# Hvamp_32.net
KiCad netlist of a schematic drawn in Altium Designer
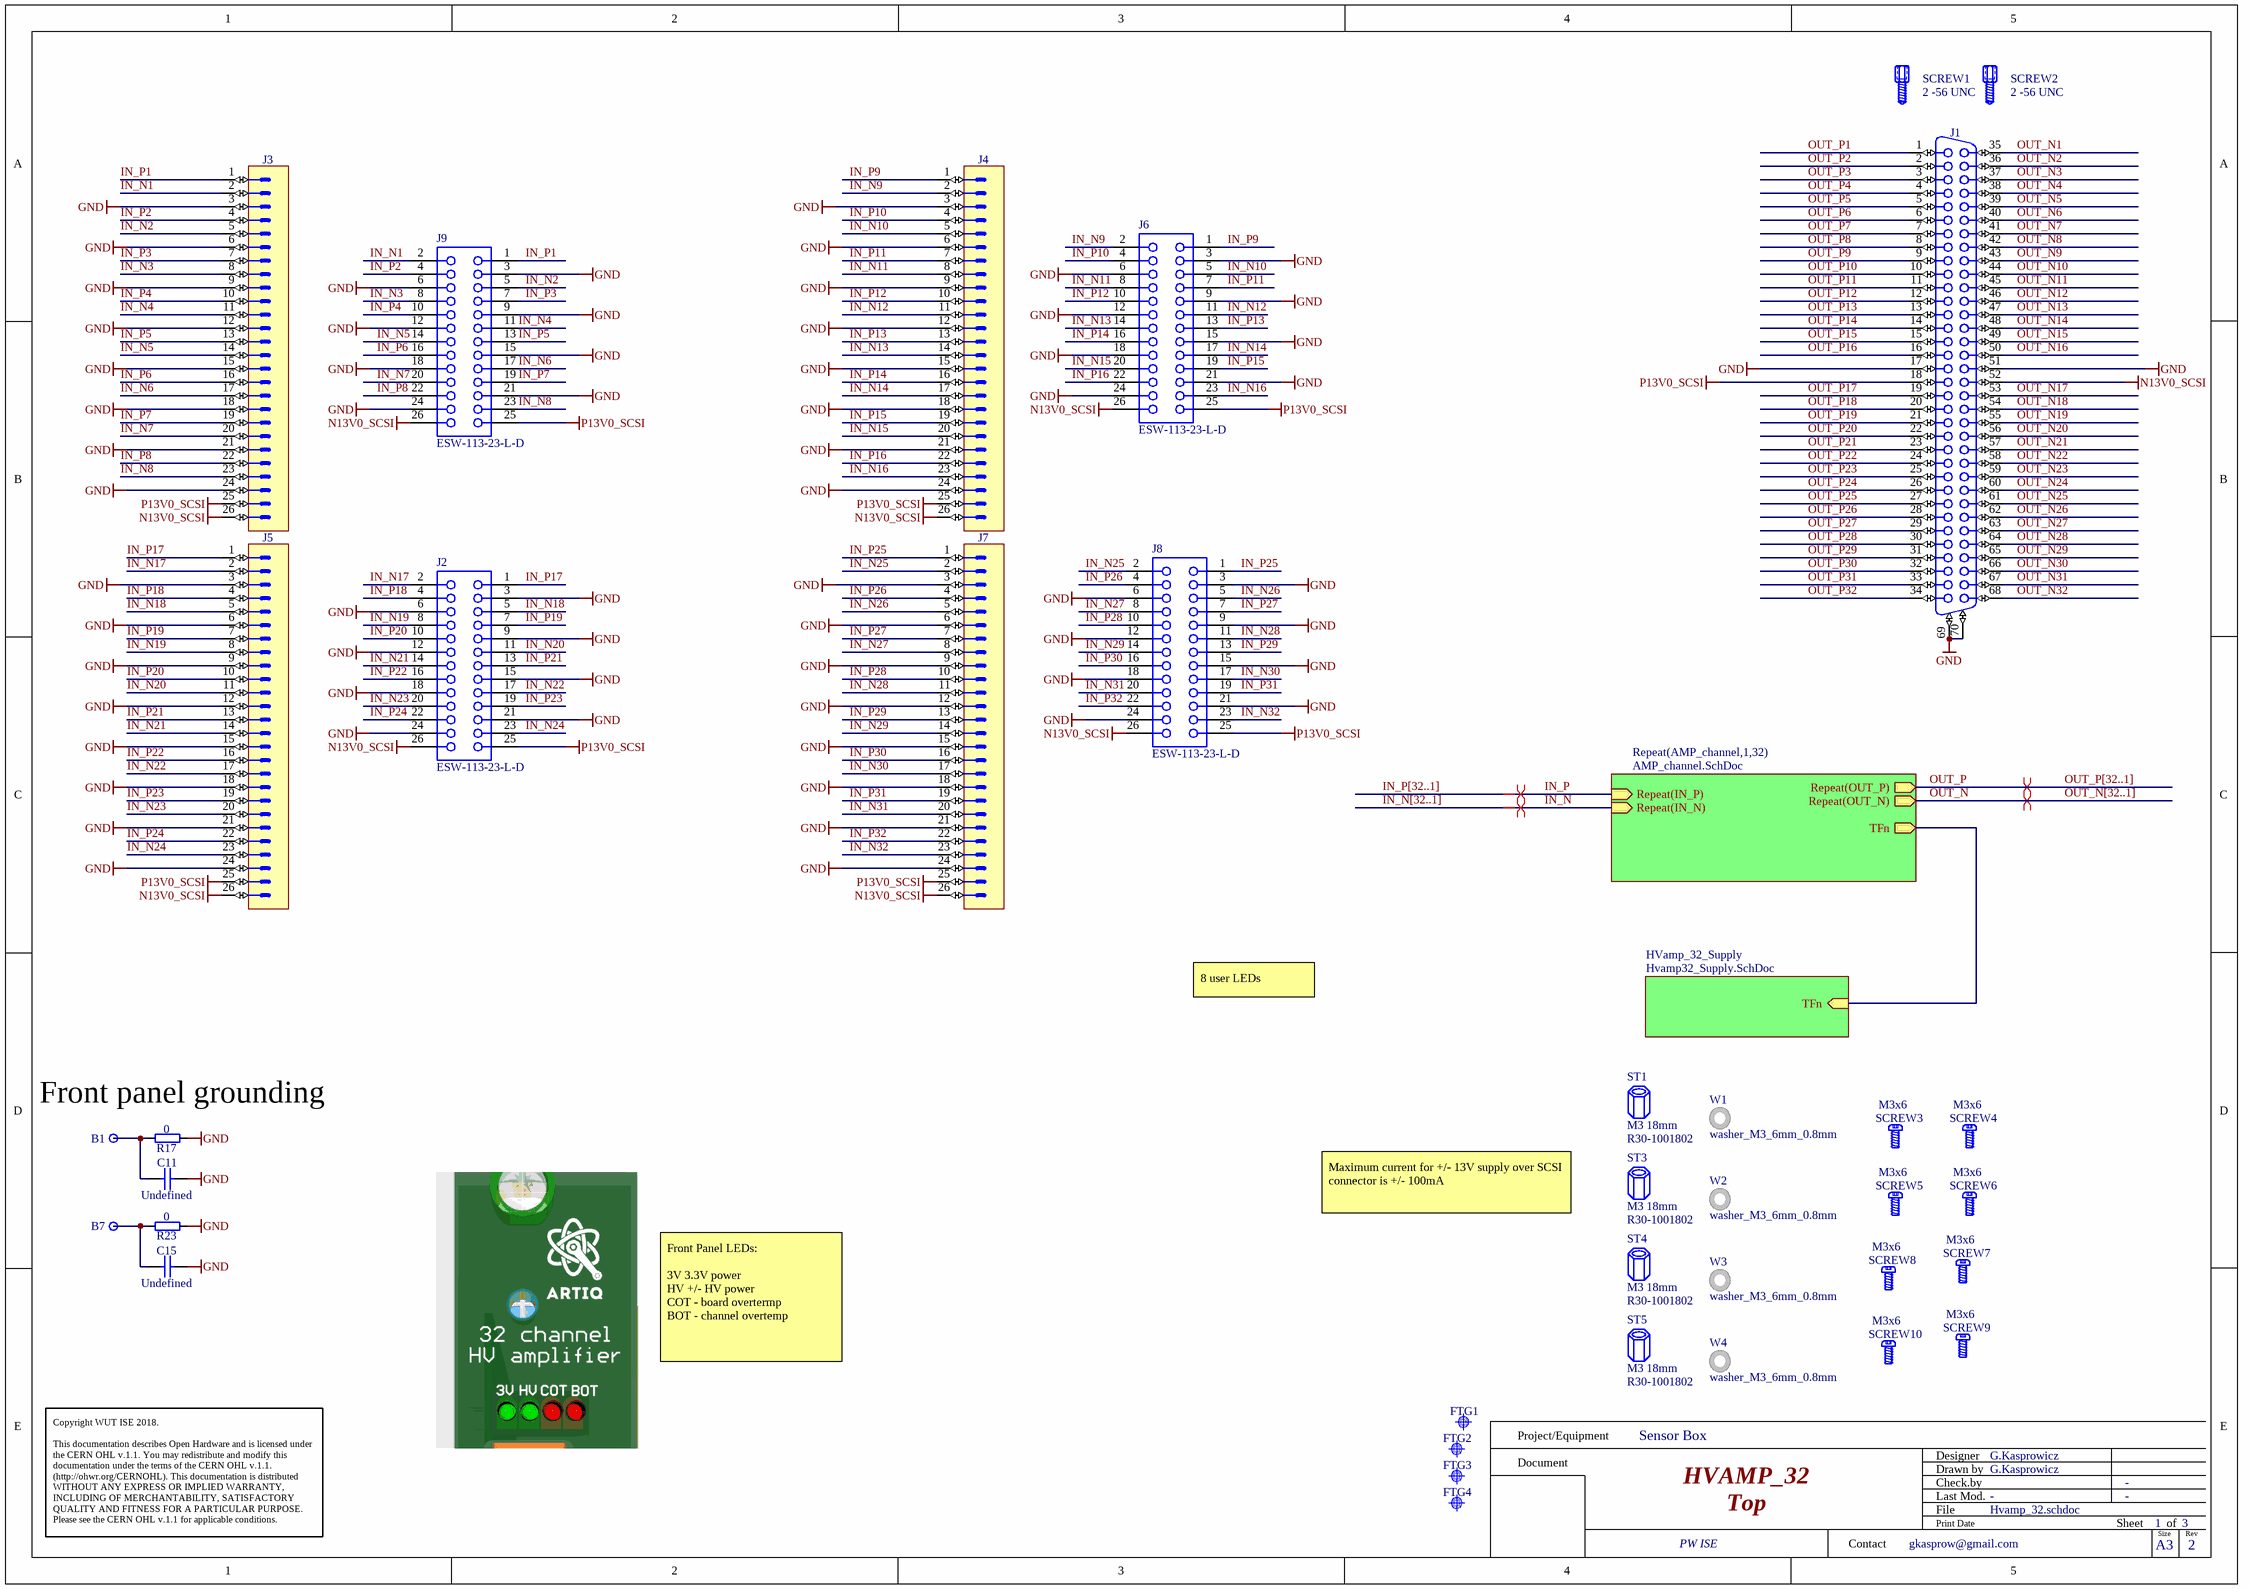
[diagram p0: Hvamp_32.schdoc]

(export (version "E")
  (design (tool "Eeschema 10.0.6"))
  (components
    (comp (ref "B1")
      (value "Plated Hole")
      (footprint "MTG270_500")
      (description "Single Terminal Socket")
      (fields (field (name "PART NUMBER") "PLATED_HOLE2.7_PAD5.0") (field (name "AUTHOR") "CERN DEM JMW"))
      (libsource (lib "Eletro-mechanical") (part "Single Terminal Socket"))
    )
    (comp (ref "B7")
      (value "Plated Hole")
      (footprint "MTG270_500")
      (description "Single Terminal Socket")
      (fields (field (name "PART NUMBER") "PLATED_HOLE2.7_PAD5.0") (field (name "AUTHOR") "CERN DEM JMW"))
      (libsource (lib "Eletro-mechanical") (part "Single Terminal Socket"))
    )
    (comp (ref "C11")
      (value "Undefined")
      (footprint "CAPC2012X135N")
      (description "Non-polarised capacitor")
      (fields (field (name "PART NUMBER") "CC0805_NO-VALUE") (field (name "AUTHOR") "CERN DEM JLC"))
      (libsource (lib "Capacitors") (part "Capacitor - non polarized"))
    )
    (comp (ref "C15")
      (value "Undefined")
      (footprint "CAPC2012X135N")
      (description "Non-polarised capacitor")
      (fields (field (name "PART NUMBER") "CC0805_NO-VALUE") (field (name "AUTHOR") "CERN DEM JLC"))
      (libsource (lib "Capacitors") (part "Capacitor - non polarized"))
    )
    (comp (ref "FTG1")
      (value "Use only in PCB")
      (footprint "FIDUCIAL_TOP_C100-200")
      (description "Fiducial Target")
      (fields (field (name "PART NUMBER") "FIDUCIAL_TARGET_C100-200") (field (name "AUTHOR") "CERN DEM JLC"))
      (libsource (lib "Eletro-mechanical") (part "Fiducial Target"))
    )
    (comp (ref "FTG2")
      (value "Use only in PCB")
      (footprint "FIDUCIAL_TOP_S100-200")
      (description "Fiducial Target")
      (fields (field (name "PART NUMBER") "FIDUCIAL_TARGET_S100-200") (field (name "AUTHOR") "CERN DEM JLC"))
      (libsource (lib "Eletro-mechanical") (part "Fiducial Target"))
    )
    (comp (ref "FTG3")
      (value "Use only in PCB")
      (footprint "FIDUCIAL_TOP_S100-200")
      (description "Fiducial Target")
      (fields (field (name "PART NUMBER") "FIDUCIAL_TARGET_S100-200") (field (name "AUTHOR") "CERN DEM JLC"))
      (libsource (lib "Eletro-mechanical") (part "Fiducial Target"))
    )
    (comp (ref "FTG4")
      (value "Use only in PCB")
      (footprint "FIDUCIAL_TOP_S100-200")
      (description "Fiducial Target")
      (fields (field (name "PART NUMBER") "FIDUCIAL_TARGET_S100-200") (field (name "AUTHOR") "CERN DEM JLC"))
      (libsource (lib "Eletro-mechanical") (part "Fiducial Target"))
    )
    (comp (ref "J1")
      (value "D-SUB")
      (footprint "TYCO_5787082-7")
      (description "68 contacts, AMPLIMITE .050\", Right Angled Receptacle Series III")
      (fields
        (field (name "PART NUMBER") "TYCO_5787082-7")
        (field (name "MANUFACTURER") "TYCO ELECTRONICS")
        (field (name "AUTHOR") "CERN DEM JLC")
      )
      (libsource (lib "Connectors") (part "TYCO_5787082-7"))
    )
    (comp (ref "J2")
      (value "ESW-113-23-L-D")
      (footprint "SMTC-ESW-113-23-X-D")
      (description "Elevated Socket, Through-hole, Vertical, -55 to 125 degC, 2.54 mm Pitch, 26-Pin, Female, RoHS")
      (fields (field (name "MANUFACTURER") "Samtec"))
      (libsource (lib "Altium Content Vault") (part "SMTC-ESW-113-X-X-D"))
    )
    (comp (ref "J3")
      (value "Header 26")
      (footprint "3M_N2526-6002RB")
      (description "Connector 26 Male")
      (fields
        (field (name "PART NUMBER") "3M_N2526-6002RB")
        (field (name "MANUFACTURER") "3M")
        (field (name "AUTHOR") "CERN DEM JLC")
      )
      (libsource (lib "Connectors") (part "Connector 26 Male"))
    )
    (comp (ref "J4")
      (value "Header 26")
      (footprint "3M_N2526-6002RB")
      (description "Connector 26 Male")
      (fields
        (field (name "PART NUMBER") "3M_N2526-6002RB")
        (field (name "MANUFACTURER") "3M")
        (field (name "AUTHOR") "CERN DEM JLC")
      )
      (libsource (lib "Connectors") (part "Connector 26 Male"))
    )
    (comp (ref "J5")
      (value "Header 26")
      (footprint "3M_N2526-6002RB")
      (description "Connector 26 Male")
      (fields
        (field (name "PART NUMBER") "3M_N2526-6002RB")
        (field (name "MANUFACTURER") "3M")
        (field (name "AUTHOR") "CERN DEM JLC")
      )
      (libsource (lib "Connectors") (part "Connector 26 Male"))
    )
    (comp (ref "J6")
      (value "ESW-113-23-L-D")
      (footprint "SMTC-ESW-113-23-X-D")
      (description "Elevated Socket, Through-hole, Vertical, -55 to 125 degC, 2.54 mm Pitch, 26-Pin, Female, RoHS")
      (fields (field (name "MANUFACTURER") "Samtec"))
      (libsource (lib "Altium Content Vault") (part "SMTC-ESW-113-X-X-D"))
    )
    (comp (ref "J7")
      (value "Header 26")
      (footprint "3M_N2526-6002RB")
      (description "Connector 26 Male")
      (fields
        (field (name "PART NUMBER") "3M_N2526-6002RB")
        (field (name "MANUFACTURER") "3M")
        (field (name "AUTHOR") "CERN DEM JLC")
      )
      (libsource (lib "Connectors") (part "Connector 26 Male"))
    )
    (comp (ref "J8")
      (value "ESW-113-23-L-D")
      (footprint "SMTC-ESW-113-23-X-D")
      (description "Elevated Socket, Through-hole, Vertical, -55 to 125 degC, 2.54 mm Pitch, 26-Pin, Female, RoHS")
      (fields (field (name "MANUFACTURER") "Samtec"))
      (libsource (lib "Altium Content Vault") (part "SMTC-ESW-113-X-X-D"))
    )
    (comp (ref "J9")
      (value "ESW-113-23-L-D")
      (footprint "SMTC-ESW-113-23-X-D")
      (description "Elevated Socket, Through-hole, Vertical, -55 to 125 degC, 2.54 mm Pitch, 26-Pin, Female, RoHS")
      (fields (field (name "MANUFACTURER") "Samtec"))
      (libsource (lib "Altium Content Vault") (part "SMTC-ESW-113-X-X-D"))
    )
    (comp (ref "R17")
      (value "0")
      (footprint "RESC1608X55N")
      (description "Resistor")
      (fields
        (field (name "PART NUMBER") "R0603_0R_JUMPER")
        (field (name "MANUFACTURER") "GENERIC")
        (field (name "AUTHOR") "CERN DEM JLC")
      )
      (libsource (lib "Resistors") (part "Resistor"))
    )
    (comp (ref "R23")
      (value "0")
      (footprint "RESC1608X55N")
      (description "Resistor")
      (fields
        (field (name "PART NUMBER") "R0603_0R_JUMPER")
        (field (name "MANUFACTURER") "GENERIC")
        (field (name "AUTHOR") "CERN DEM JLC")
      )
      (libsource (lib "Resistors") (part "Resistor"))
    )
    (comp (ref "SCREW1")
      (value "2 -56 UNC")
      (footprint "TYCO_786585-2")
      (description "SCSI Screw Lock")
      (fields
        (field (name "PART NUMBER") "TYCO_786585-2")
        (field (name "MANUFACTURER") "TYCO ELECTRONICS")
        (field (name "AUTHOR") "GK")
      )
      (libsource (lib "LIBRARY_SCH") (part "MECH_Tyco_SCSI_Screwlock"))
    )
    (comp (ref "SCREW2")
      (value "2 -56 UNC")
      (footprint "TYCO_786585-2")
      (description "SCSI Screw Lock")
      (fields
        (field (name "PART NUMBER") "TYCO_786585-2")
        (field (name "MANUFACTURER") "TYCO ELECTRONICS")
        (field (name "AUTHOR") "GK")
      )
      (libsource (lib "LIBRARY_SCH") (part "MECH_Tyco_SCSI_Screwlock"))
    )
    (comp (ref "SCREW3")
      (value "M3x6")
      (footprint "BOSSARD_BN5687-3061605_v")
      (description "Screw")
      (fields
        (field (name "PART NUMBER") "BOSSARD_BN5687-3061605_v")
        (field (name "MANUFACTURER") "BOSSARD")
        (field (name "AUTHOR") "CERN DEM JLC")
      )
      (libsource (lib "Eletro-mechanical") (part "Screw"))
    )
    (comp (ref "SCREW4")
      (value "M3x6")
      (footprint "BOSSARD_BN5687-3061605_v")
      (description "Screw")
      (fields
        (field (name "PART NUMBER") "BOSSARD_BN5687-3061605_v")
        (field (name "MANUFACTURER") "BOSSARD")
        (field (name "AUTHOR") "CERN DEM JLC")
      )
      (libsource (lib "Eletro-mechanical") (part "Screw"))
    )
    (comp (ref "SCREW5")
      (value "M3x6")
      (footprint "BOSSARD_BN5687-3061605_v")
      (description "Screw")
      (fields
        (field (name "PART NUMBER") "BOSSARD_BN5687-3061605_v")
        (field (name "MANUFACTURER") "BOSSARD")
        (field (name "AUTHOR") "CERN DEM JLC")
      )
      (libsource (lib "Eletro-mechanical") (part "Screw"))
    )
    (comp (ref "SCREW6")
      (value "M3x6")
      (footprint "BOSSARD_BN5687-3061605_v")
      (description "Screw")
      (fields
        (field (name "PART NUMBER") "BOSSARD_BN5687-3061605_v")
        (field (name "MANUFACTURER") "BOSSARD")
        (field (name "AUTHOR") "CERN DEM JLC")
      )
      (libsource (lib "Eletro-mechanical") (part "Screw"))
    )
    (comp (ref "SCREW7")
      (value "M3x6")
      (footprint "BOSSARD_BN5687-3061605_v")
      (description "Screw")
      (fields
        (field (name "PART NUMBER") "BOSSARD_BN5687-3061605_v")
        (field (name "MANUFACTURER") "BOSSARD")
        (field (name "AUTHOR") "CERN DEM JLC")
      )
      (libsource (lib "Eletro-mechanical") (part "Screw"))
    )
    (comp (ref "SCREW8")
      (value "M3x6")
      (footprint "BOSSARD_BN5687-3061605_v")
      (description "Screw")
      (fields
        (field (name "PART NUMBER") "BOSSARD_BN5687-3061605_v")
        (field (name "MANUFACTURER") "BOSSARD")
        (field (name "AUTHOR") "CERN DEM JLC")
      )
      (libsource (lib "Eletro-mechanical") (part "Screw"))
    )
    (comp (ref "SCREW9")
      (value "M3x6")
      (footprint "BOSSARD_BN5687-3061605_v")
      (description "Screw")
      (fields
        (field (name "PART NUMBER") "BOSSARD_BN5687-3061605_v")
        (field (name "MANUFACTURER") "BOSSARD")
        (field (name "AUTHOR") "CERN DEM JLC")
      )
      (libsource (lib "Eletro-mechanical") (part "Screw"))
    )
    (comp (ref "SCREW10")
      (value "M3x6")
      (footprint "BOSSARD_BN5687-3061605_v")
      (description "Screw")
      (fields
        (field (name "PART NUMBER") "BOSSARD_BN5687-3061605_v")
        (field (name "MANUFACTURER") "BOSSARD")
        (field (name "AUTHOR") "CERN DEM JLC")
      )
      (libsource (lib "Eletro-mechanical") (part "Screw"))
    )
    (comp (ref "ST1")
      (value "M3 18mm")
      (footprint "R30-1001802")
      (description "M3.0x18 standoff")
      (fields (field (name "MANUFACTURER") "Harwin") (field (name "MANUFACTURER PART NUMBER") "R30-1001802"))
      (libsource (lib "mechanical") (part "STANDOFF_HARWIN_R30_1001802"))
    )
    (comp (ref "ST3")
      (value "M3 18mm")
      (footprint "R30-1001802")
      (description "M3.0x18 standoff")
      (fields (field (name "MANUFACTURER") "Harwin") (field (name "MANUFACTURER PART NUMBER") "R30-1001802"))
      (libsource (lib "mechanical") (part "STANDOFF_HARWIN_R30_1001802"))
    )
    (comp (ref "ST4")
      (value "M3 18mm")
      (footprint "R30-1001802")
      (description "M3.0x18 standoff")
      (fields (field (name "MANUFACTURER") "Harwin") (field (name "MANUFACTURER PART NUMBER") "R30-1001802"))
      (libsource (lib "mechanical") (part "STANDOFF_HARWIN_R30_1001802"))
    )
    (comp (ref "ST5")
      (value "M3 18mm")
      (footprint "R30-1001802")
      (description "M3.0x18 standoff")
      (fields (field (name "MANUFACTURER") "Harwin") (field (name "MANUFACTURER PART NUMBER") "R30-1001802"))
      (libsource (lib "mechanical") (part "STANDOFF_HARWIN_R30_1001802"))
    )
    (comp (ref "W1")
      (value "washer_M3_6mm_0.8mm")
      (footprint "washer_M3_6mm_0.8mm")
      (description "M3 Washer:\r\nID: 3.2mm\r\nOD: 6mm\r\nThickness 0.8mm")
      (fields
        (field (name "MANUFACTURER") "Accu Limited")
        (field (name "MANUFACTURER PART NUMBER") "HAFZ-M3-A4")
      )
      (libsource (lib "mechanical") (part "washer_M3_6mm_0.8mm"))
    )
    (comp (ref "W2")
      (value "washer_M3_6mm_0.8mm")
      (footprint "washer_M3_6mm_0.8mm")
      (description "M3 Washer:\r\nID: 3.2mm\r\nOD: 6mm\r\nThickness 0.8mm")
      (fields
        (field (name "MANUFACTURER") "Accu Limited")
        (field (name "MANUFACTURER PART NUMBER") "HAFZ-M3-A4")
      )
      (libsource (lib "mechanical") (part "washer_M3_6mm_0.8mm"))
    )
    (comp (ref "W3")
      (value "washer_M3_6mm_0.8mm")
      (footprint "washer_M3_6mm_0.8mm")
      (description "M3 Washer:\r\nID: 3.2mm\r\nOD: 6mm\r\nThickness 0.8mm")
      (fields
        (field (name "MANUFACTURER") "Accu Limited")
        (field (name "MANUFACTURER PART NUMBER") "HAFZ-M3-A4")
      )
      (libsource (lib "mechanical") (part "washer_M3_6mm_0.8mm"))
    )
    (comp (ref "W4")
      (value "washer_M3_6mm_0.8mm")
      (footprint "washer_M3_6mm_0.8mm")
      (description "M3 Washer:\r\nID: 3.2mm\r\nOD: 6mm\r\nThickness 0.8mm")
      (fields
        (field (name "MANUFACTURER") "Accu Limited")
        (field (name "MANUFACTURER PART NUMBER") "HAFZ-M3-A4")
      )
      (libsource (lib "mechanical") (part "washer_M3_6mm_0.8mm"))
    )
  )
  (nets
    (net (code "2") (name "/IN_N1") (class "Default")
      (node (ref "J3") (pin "2") (pinfunction "2_2") (pintype "bidirectional"))
      (node (ref "J9") (pin "2") (pinfunction "2_2") (pintype "passive"))
    )
    (net (code "3") (name "/IN_N2") (class "Default")
      (node (ref "J3") (pin "5") (pinfunction "5_5") (pintype "bidirectional"))
      (node (ref "J9") (pin "5") (pinfunction "5_5") (pintype "passive"))
    )
    (net (code "4") (name "/IN_N3") (class "Default")
      (node (ref "J3") (pin "8") (pinfunction "8_8") (pintype "bidirectional"))
      (node (ref "J9") (pin "8") (pinfunction "8_8") (pintype "passive"))
    )
    (net (code "5") (name "/IN_N4") (class "Default")
      (node (ref "J3") (pin "11") (pinfunction "11_11") (pintype "bidirectional"))
      (node (ref "J9") (pin "11") (pinfunction "11_11") (pintype "passive"))
    )
    (net (code "6") (name "/IN_N5") (class "Default")
      (node (ref "J3") (pin "14") (pinfunction "14_14") (pintype "bidirectional"))
      (node (ref "J9") (pin "14") (pinfunction "14_14") (pintype "passive"))
    )
    (net (code "7") (name "/IN_N6") (class "Default")
      (node (ref "J3") (pin "17") (pinfunction "17_17") (pintype "bidirectional"))
      (node (ref "J9") (pin "17") (pinfunction "17_17") (pintype "passive"))
    )
    (net (code "8") (name "/IN_N7") (class "Default")
      (node (ref "J3") (pin "20") (pinfunction "20_20") (pintype "bidirectional"))
      (node (ref "J9") (pin "20") (pinfunction "20_20") (pintype "passive"))
    )
    (net (code "9") (name "/IN_N8") (class "Default")
      (node (ref "J3") (pin "23") (pinfunction "23_23") (pintype "bidirectional"))
      (node (ref "J9") (pin "23") (pinfunction "23_23") (pintype "passive"))
    )
    (net (code "10") (name "/IN_N9") (class "Default")
      (node (ref "J4") (pin "2") (pinfunction "2_2") (pintype "bidirectional"))
      (node (ref "J6") (pin "2") (pinfunction "2_2") (pintype "passive"))
    )
    (net (code "11") (name "/IN_N10") (class "Default")
      (node (ref "J4") (pin "5") (pinfunction "5_5") (pintype "bidirectional"))
      (node (ref "J6") (pin "5") (pinfunction "5_5") (pintype "passive"))
    )
    (net (code "12") (name "/IN_N11") (class "Default")
      (node (ref "J4") (pin "8") (pinfunction "8_8") (pintype "bidirectional"))
      (node (ref "J6") (pin "8") (pinfunction "8_8") (pintype "passive"))
    )
    (net (code "13") (name "/IN_N12") (class "Default")
      (node (ref "J4") (pin "11") (pinfunction "11_11") (pintype "bidirectional"))
      (node (ref "J6") (pin "11") (pinfunction "11_11") (pintype "passive"))
    )
    (net (code "14") (name "/IN_N13") (class "Default")
      (node (ref "J4") (pin "14") (pinfunction "14_14") (pintype "bidirectional"))
      (node (ref "J6") (pin "14") (pinfunction "14_14") (pintype "passive"))
    )
    (net (code "15") (name "/IN_N14") (class "Default")
      (node (ref "J4") (pin "17") (pinfunction "17_17") (pintype "bidirectional"))
      (node (ref "J6") (pin "17") (pinfunction "17_17") (pintype "passive"))
    )
    (net (code "16") (name "/IN_N15") (class "Default")
      (node (ref "J4") (pin "20") (pinfunction "20_20") (pintype "bidirectional"))
      (node (ref "J6") (pin "20") (pinfunction "20_20") (pintype "passive"))
    )
    (net (code "17") (name "/IN_N16") (class "Default")
      (node (ref "J4") (pin "23") (pinfunction "23_23") (pintype "bidirectional"))
      (node (ref "J6") (pin "23") (pinfunction "23_23") (pintype "passive"))
    )
    (net (code "18") (name "/IN_N17") (class "Default")
      (node (ref "J2") (pin "2") (pinfunction "2_2") (pintype "passive"))
      (node (ref "J5") (pin "2") (pinfunction "2_2") (pintype "bidirectional"))
    )
    (net (code "19") (name "/IN_N18") (class "Default")
      (node (ref "J2") (pin "5") (pinfunction "5_5") (pintype "passive"))
      (node (ref "J5") (pin "5") (pinfunction "5_5") (pintype "bidirectional"))
    )
    (net (code "20") (name "/IN_N19") (class "Default")
      (node (ref "J2") (pin "8") (pinfunction "8_8") (pintype "passive"))
      (node (ref "J5") (pin "8") (pinfunction "8_8") (pintype "bidirectional"))
    )
    (net (code "21") (name "/IN_N20") (class "Default")
      (node (ref "J2") (pin "11") (pinfunction "11_11") (pintype "passive"))
      (node (ref "J5") (pin "11") (pinfunction "11_11") (pintype "bidirectional"))
    )
    (net (code "22") (name "/IN_N21") (class "Default")
      (node (ref "J2") (pin "14") (pinfunction "14_14") (pintype "passive"))
      (node (ref "J5") (pin "14") (pinfunction "14_14") (pintype "bidirectional"))
    )
    (net (code "23") (name "/IN_N22") (class "Default")
      (node (ref "J2") (pin "17") (pinfunction "17_17") (pintype "passive"))
      (node (ref "J5") (pin "17") (pinfunction "17_17") (pintype "bidirectional"))
    )
    (net (code "24") (name "/IN_N23") (class "Default")
      (node (ref "J2") (pin "20") (pinfunction "20_20") (pintype "passive"))
      (node (ref "J5") (pin "20") (pinfunction "20_20") (pintype "bidirectional"))
    )
    (net (code "25") (name "/IN_N24") (class "Default")
      (node (ref "J2") (pin "23") (pinfunction "23_23") (pintype "passive"))
      (node (ref "J5") (pin "23") (pinfunction "23_23") (pintype "bidirectional"))
    )
    (net (code "26") (name "/IN_N25") (class "Default")
      (node (ref "J7") (pin "2") (pinfunction "2_2") (pintype "bidirectional"))
      (node (ref "J8") (pin "2") (pinfunction "2_2") (pintype "passive"))
    )
    (net (code "27") (name "/IN_N26") (class "Default")
      (node (ref "J7") (pin "5") (pinfunction "5_5") (pintype "bidirectional"))
      (node (ref "J8") (pin "5") (pinfunction "5_5") (pintype "passive"))
    )
    (net (code "28") (name "/IN_N27") (class "Default")
      (node (ref "J7") (pin "8") (pinfunction "8_8") (pintype "bidirectional"))
      (node (ref "J8") (pin "8") (pinfunction "8_8") (pintype "passive"))
    )
    (net (code "29") (name "/IN_N28") (class "Default")
      (node (ref "J7") (pin "11") (pinfunction "11_11") (pintype "bidirectional"))
      (node (ref "J8") (pin "11") (pinfunction "11_11") (pintype "passive"))
    )
    (net (code "30") (name "/IN_N29") (class "Default")
      (node (ref "J7") (pin "14") (pinfunction "14_14") (pintype "bidirectional"))
      (node (ref "J8") (pin "14") (pinfunction "14_14") (pintype "passive"))
    )
    (net (code "31") (name "/IN_N30") (class "Default")
      (node (ref "J7") (pin "17") (pinfunction "17_17") (pintype "bidirectional"))
      (node (ref "J8") (pin "17") (pinfunction "17_17") (pintype "passive"))
    )
    (net (code "32") (name "/IN_N31") (class "Default")
      (node (ref "J7") (pin "20") (pinfunction "20_20") (pintype "bidirectional"))
      (node (ref "J8") (pin "20") (pinfunction "20_20") (pintype "passive"))
    )
    (net (code "33") (name "/IN_N32") (class "Default")
      (node (ref "J7") (pin "23") (pinfunction "23_23") (pintype "bidirectional"))
      (node (ref "J8") (pin "23") (pinfunction "23_23") (pintype "passive"))
    )
    (net (code "36") (name "/IN_P1") (class "Default")
      (node (ref "J3") (pin "1") (pinfunction "1_1") (pintype "bidirectional"))
      (node (ref "J9") (pin "1") (pinfunction "1_1") (pintype "passive"))
    )
    (net (code "37") (name "/IN_P2") (class "Default")
      (node (ref "J3") (pin "4") (pinfunction "4_4") (pintype "bidirectional"))
      (node (ref "J9") (pin "4") (pinfunction "4_4") (pintype "passive"))
    )
    (net (code "38") (name "/IN_P3") (class "Default")
      (node (ref "J3") (pin "7") (pinfunction "7_7") (pintype "bidirectional"))
      (node (ref "J9") (pin "7") (pinfunction "7_7") (pintype "passive"))
    )
    (net (code "39") (name "/IN_P4") (class "Default")
      (node (ref "J3") (pin "10") (pinfunction "10_10") (pintype "bidirectional"))
      (node (ref "J9") (pin "10") (pinfunction "10_10") (pintype "passive"))
    )
    (net (code "40") (name "/IN_P5") (class "Default")
      (node (ref "J3") (pin "13") (pinfunction "13_13") (pintype "bidirectional"))
      (node (ref "J9") (pin "13") (pinfunction "13_13") (pintype "passive"))
    )
    (net (code "41") (name "/IN_P6") (class "Default")
      (node (ref "J3") (pin "16") (pinfunction "16_16") (pintype "bidirectional"))
      (node (ref "J9") (pin "16") (pinfunction "16_16") (pintype "passive"))
    )
    (net (code "42") (name "/IN_P7") (class "Default")
      (node (ref "J3") (pin "19") (pinfunction "19_19") (pintype "bidirectional"))
      (node (ref "J9") (pin "19") (pinfunction "19_19") (pintype "passive"))
    )
    (net (code "43") (name "/IN_P8") (class "Default")
      (node (ref "J3") (pin "22") (pinfunction "22_22") (pintype "bidirectional"))
      (node (ref "J9") (pin "22") (pinfunction "22_22") (pintype "passive"))
    )
    (net (code "44") (name "/IN_P9") (class "Default")
      (node (ref "J4") (pin "1") (pinfunction "1_1") (pintype "bidirectional"))
      (node (ref "J6") (pin "1") (pinfunction "1_1") (pintype "passive"))
    )
    (net (code "45") (name "/IN_P10") (class "Default")
      (node (ref "J4") (pin "4") (pinfunction "4_4") (pintype "bidirectional"))
      (node (ref "J6") (pin "4") (pinfunction "4_4") (pintype "passive"))
    )
    (net (code "46") (name "/IN_P11") (class "Default")
      (node (ref "J4") (pin "7") (pinfunction "7_7") (pintype "bidirectional"))
      (node (ref "J6") (pin "7") (pinfunction "7_7") (pintype "passive"))
    )
    (net (code "47") (name "/IN_P12") (class "Default")
      (node (ref "J4") (pin "10") (pinfunction "10_10") (pintype "bidirectional"))
      (node (ref "J6") (pin "10") (pinfunction "10_10") (pintype "passive"))
    )
    (net (code "48") (name "/IN_P13") (class "Default")
      (node (ref "J4") (pin "13") (pinfunction "13_13") (pintype "bidirectional"))
      (node (ref "J6") (pin "13") (pinfunction "13_13") (pintype "passive"))
    )
    (net (code "49") (name "/IN_P14") (class "Default")
      (node (ref "J4") (pin "16") (pinfunction "16_16") (pintype "bidirectional"))
      (node (ref "J6") (pin "16") (pinfunction "16_16") (pintype "passive"))
    )
    (net (code "50") (name "/IN_P15") (class "Default")
      (node (ref "J4") (pin "19") (pinfunction "19_19") (pintype "bidirectional"))
      (node (ref "J6") (pin "19") (pinfunction "19_19") (pintype "passive"))
    )
    (net (code "51") (name "/IN_P16") (class "Default")
      (node (ref "J4") (pin "22") (pinfunction "22_22") (pintype "bidirectional"))
      (node (ref "J6") (pin "22") (pinfunction "22_22") (pintype "passive"))
    )
    (net (code "52") (name "/IN_P17") (class "Default")
      (node (ref "J2") (pin "1") (pinfunction "1_1") (pintype "passive"))
      (node (ref "J5") (pin "1") (pinfunction "1_1") (pintype "bidirectional"))
    )
    (net (code "53") (name "/IN_P18") (class "Default")
      (node (ref "J2") (pin "4") (pinfunction "4_4") (pintype "passive"))
      (node (ref "J5") (pin "4") (pinfunction "4_4") (pintype "bidirectional"))
    )
    (net (code "54") (name "/IN_P19") (class "Default")
      (node (ref "J2") (pin "7") (pinfunction "7_7") (pintype "passive"))
      (node (ref "J5") (pin "7") (pinfunction "7_7") (pintype "bidirectional"))
    )
    (net (code "55") (name "/IN_P20") (class "Default")
      (node (ref "J2") (pin "10") (pinfunction "10_10") (pintype "passive"))
      (node (ref "J5") (pin "10") (pinfunction "10_10") (pintype "bidirectional"))
    )
    (net (code "56") (name "/IN_P21") (class "Default")
      (node (ref "J2") (pin "13") (pinfunction "13_13") (pintype "passive"))
      (node (ref "J5") (pin "13") (pinfunction "13_13") (pintype "bidirectional"))
    )
    (net (code "57") (name "/IN_P22") (class "Default")
      (node (ref "J2") (pin "16") (pinfunction "16_16") (pintype "passive"))
      (node (ref "J5") (pin "16") (pinfunction "16_16") (pintype "bidirectional"))
    )
    (net (code "58") (name "/IN_P23") (class "Default")
      (node (ref "J2") (pin "19") (pinfunction "19_19") (pintype "passive"))
      (node (ref "J5") (pin "19") (pinfunction "19_19") (pintype "bidirectional"))
    )
    (net (code "59") (name "/IN_P24") (class "Default")
      (node (ref "J2") (pin "22") (pinfunction "22_22") (pintype "passive"))
      (node (ref "J5") (pin "22") (pinfunction "22_22") (pintype "bidirectional"))
    )
    (net (code "60") (name "/IN_P25") (class "Default")
      (node (ref "J7") (pin "1") (pinfunction "1_1") (pintype "bidirectional"))
      (node (ref "J8") (pin "1") (pinfunction "1_1") (pintype "passive"))
    )
    (net (code "61") (name "/IN_P26") (class "Default")
      (node (ref "J7") (pin "4") (pinfunction "4_4") (pintype "bidirectional"))
      (node (ref "J8") (pin "4") (pinfunction "4_4") (pintype "passive"))
    )
    (net (code "62") (name "/IN_P27") (class "Default")
      (node (ref "J7") (pin "7") (pinfunction "7_7") (pintype "bidirectional"))
      (node (ref "J8") (pin "7") (pinfunction "7_7") (pintype "passive"))
    )
    (net (code "63") (name "/IN_P28") (class "Default")
      (node (ref "J7") (pin "10") (pinfunction "10_10") (pintype "bidirectional"))
      (node (ref "J8") (pin "10") (pinfunction "10_10") (pintype "passive"))
    )
    (net (code "64") (name "/IN_P29") (class "Default")
      (node (ref "J7") (pin "13") (pinfunction "13_13") (pintype "bidirectional"))
      (node (ref "J8") (pin "13") (pinfunction "13_13") (pintype "passive"))
    )
    (net (code "65") (name "/IN_P30") (class "Default")
      (node (ref "J7") (pin "16") (pinfunction "16_16") (pintype "bidirectional"))
      (node (ref "J8") (pin "16") (pinfunction "16_16") (pintype "passive"))
    )
    (net (code "66") (name "/IN_P31") (class "Default")
      (node (ref "J7") (pin "19") (pinfunction "19_19") (pintype "bidirectional"))
      (node (ref "J8") (pin "19") (pinfunction "19_19") (pintype "passive"))
    )
    (net (code "67") (name "/IN_P32") (class "Default")
      (node (ref "J7") (pin "22") (pinfunction "22_22") (pintype "bidirectional"))
      (node (ref "J8") (pin "22") (pinfunction "22_22") (pintype "passive"))
    )
    (net (code "70") (name "/OUT_N1") (class "Default")
      (node (ref "J1") (pin "35") (pinfunction "35_35") (pintype "bidirectional"))
    )
    (net (code "71") (name "/OUT_N2") (class "Default")
      (node (ref "J1") (pin "36") (pinfunction "36_36") (pintype "bidirectional"))
    )
    (net (code "72") (name "/OUT_N3") (class "Default")
      (node (ref "J1") (pin "37") (pinfunction "37_37") (pintype "bidirectional"))
    )
    (net (code "73") (name "/OUT_N4") (class "Default")
      (node (ref "J1") (pin "38") (pinfunction "38_38") (pintype "bidirectional"))
    )
    (net (code "74") (name "/OUT_N5") (class "Default")
      (node (ref "J1") (pin "39") (pinfunction "39_39") (pintype "bidirectional"))
    )
    (net (code "75") (name "/OUT_N6") (class "Default")
      (node (ref "J1") (pin "40") (pinfunction "40_40") (pintype "bidirectional"))
    )
    (net (code "76") (name "/OUT_N7") (class "Default")
      (node (ref "J1") (pin "41") (pinfunction "41_41") (pintype "bidirectional"))
    )
    (net (code "77") (name "/OUT_N8") (class "Default")
      (node (ref "J1") (pin "42") (pinfunction "42_42") (pintype "bidirectional"))
    )
    (net (code "78") (name "/OUT_N9") (class "Default")
      (node (ref "J1") (pin "43") (pinfunction "43_43") (pintype "bidirectional"))
    )
    (net (code "79") (name "/OUT_N10") (class "Default")
      (node (ref "J1") (pin "44") (pinfunction "44_44") (pintype "bidirectional"))
    )
    (net (code "80") (name "/OUT_N11") (class "Default")
      (node (ref "J1") (pin "45") (pinfunction "45_45") (pintype "bidirectional"))
    )
    (net (code "81") (name "/OUT_N12") (class "Default")
      (node (ref "J1") (pin "46") (pinfunction "46_46") (pintype "bidirectional"))
    )
    (net (code "82") (name "/OUT_N13") (class "Default")
      (node (ref "J1") (pin "47") (pinfunction "47_47") (pintype "bidirectional"))
    )
    (net (code "83") (name "/OUT_N14") (class "Default")
      (node (ref "J1") (pin "48") (pinfunction "48_48") (pintype "bidirectional"))
    )
    (net (code "84") (name "/OUT_N15") (class "Default")
      (node (ref "J1") (pin "49") (pinfunction "49_49") (pintype "bidirectional"))
    )
    (net (code "85") (name "/OUT_N16") (class "Default")
      (node (ref "J1") (pin "50") (pinfunction "50_50") (pintype "bidirectional"))
    )
    (net (code "86") (name "/OUT_N17") (class "Default")
      (node (ref "J1") (pin "53") (pinfunction "53_53") (pintype "bidirectional"))
    )
    (net (code "87") (name "/OUT_N18") (class "Default")
      (node (ref "J1") (pin "54") (pinfunction "54_54") (pintype "bidirectional"))
    )
    (net (code "88") (name "/OUT_N19") (class "Default")
      (node (ref "J1") (pin "55") (pinfunction "55_55") (pintype "bidirectional"))
    )
    (net (code "89") (name "/OUT_N20") (class "Default")
      (node (ref "J1") (pin "56") (pinfunction "56_56") (pintype "bidirectional"))
    )
    (net (code "90") (name "/OUT_N21") (class "Default")
      (node (ref "J1") (pin "57") (pinfunction "57_57") (pintype "bidirectional"))
    )
    (net (code "91") (name "/OUT_N22") (class "Default")
      (node (ref "J1") (pin "58") (pinfunction "58_58") (pintype "bidirectional"))
    )
    (net (code "92") (name "/OUT_N23") (class "Default")
      (node (ref "J1") (pin "59") (pinfunction "59_59") (pintype "bidirectional"))
    )
    (net (code "93") (name "/OUT_N24") (class "Default")
      (node (ref "J1") (pin "60") (pinfunction "60_60") (pintype "bidirectional"))
    )
    (net (code "94") (name "/OUT_N25") (class "Default")
      (node (ref "J1") (pin "61") (pinfunction "61_61") (pintype "bidirectional"))
    )
    (net (code "95") (name "/OUT_N26") (class "Default")
      (node (ref "J1") (pin "62") (pinfunction "62_62") (pintype "bidirectional"))
    )
    (net (code "96") (name "/OUT_N27") (class "Default")
      (node (ref "J1") (pin "63") (pinfunction "63_63") (pintype "bidirectional"))
    )
    (net (code "97") (name "/OUT_N28") (class "Default")
      (node (ref "J1") (pin "64") (pinfunction "64_64") (pintype "bidirectional"))
    )
    (net (code "98") (name "/OUT_N29") (class "Default")
      (node (ref "J1") (pin "65") (pinfunction "65_65") (pintype "bidirectional"))
    )
    (net (code "99") (name "/OUT_N30") (class "Default")
      (node (ref "J1") (pin "66") (pinfunction "66_66") (pintype "bidirectional"))
    )
    (net (code "100") (name "/OUT_N31") (class "Default")
      (node (ref "J1") (pin "67") (pinfunction "67_67") (pintype "bidirectional"))
    )
    (net (code "101") (name "/OUT_N32") (class "Default")
      (node (ref "J1") (pin "68") (pinfunction "68_68") (pintype "bidirectional"))
    )
    (net (code "104") (name "/OUT_P1") (class "Default")
      (node (ref "J1") (pin "1") (pinfunction "1_1") (pintype "bidirectional"))
    )
    (net (code "105") (name "/OUT_P2") (class "Default")
      (node (ref "J1") (pin "2") (pinfunction "2_2") (pintype "bidirectional"))
    )
    (net (code "106") (name "/OUT_P3") (class "Default")
      (node (ref "J1") (pin "3") (pinfunction "3_3") (pintype "bidirectional"))
    )
    (net (code "107") (name "/OUT_P4") (class "Default")
      (node (ref "J1") (pin "4") (pinfunction "4_4") (pintype "bidirectional"))
    )
    (net (code "108") (name "/OUT_P5") (class "Default")
      (node (ref "J1") (pin "5") (pinfunction "5_5") (pintype "bidirectional"))
    )
    (net (code "109") (name "/OUT_P6") (class "Default")
      (node (ref "J1") (pin "6") (pinfunction "6_6") (pintype "bidirectional"))
    )
    (net (code "110") (name "/OUT_P7") (class "Default")
      (node (ref "J1") (pin "7") (pinfunction "7_7") (pintype "bidirectional"))
    )
    (net (code "111") (name "/OUT_P8") (class "Default")
      (node (ref "J1") (pin "8") (pinfunction "8_8") (pintype "bidirectional"))
    )
    (net (code "112") (name "/OUT_P9") (class "Default")
      (node (ref "J1") (pin "9") (pinfunction "9_9") (pintype "bidirectional"))
    )
    (net (code "113") (name "/OUT_P10") (class "Default")
      (node (ref "J1") (pin "10") (pinfunction "10_10") (pintype "bidirectional"))
    )
    (net (code "114") (name "/OUT_P11") (class "Default")
      (node (ref "J1") (pin "11") (pinfunction "11_11") (pintype "bidirectional"))
    )
    (net (code "115") (name "/OUT_P12") (class "Default")
      (node (ref "J1") (pin "12") (pinfunction "12_12") (pintype "bidirectional"))
    )
    (net (code "116") (name "/OUT_P13") (class "Default")
      (node (ref "J1") (pin "13") (pinfunction "13_13") (pintype "bidirectional"))
    )
    (net (code "117") (name "/OUT_P14") (class "Default")
      (node (ref "J1") (pin "14") (pinfunction "14_14") (pintype "bidirectional"))
    )
    (net (code "118") (name "/OUT_P15") (class "Default")
      (node (ref "J1") (pin "15") (pinfunction "15_15") (pintype "bidirectional"))
    )
    (net (code "119") (name "/OUT_P16") (class "Default")
      (node (ref "J1") (pin "16") (pinfunction "16_16") (pintype "bidirectional"))
    )
    (net (code "120") (name "/OUT_P17") (class "Default")
      (node (ref "J1") (pin "19") (pinfunction "19_19") (pintype "bidirectional"))
    )
    (net (code "121") (name "/OUT_P18") (class "Default")
      (node (ref "J1") (pin "20") (pinfunction "20_20") (pintype "bidirectional"))
    )
    (net (code "122") (name "/OUT_P19") (class "Default")
      (node (ref "J1") (pin "21") (pinfunction "21_21") (pintype "bidirectional"))
    )
    (net (code "123") (name "/OUT_P20") (class "Default")
      (node (ref "J1") (pin "22") (pinfunction "22_22") (pintype "bidirectional"))
    )
    (net (code "124") (name "/OUT_P21") (class "Default")
      (node (ref "J1") (pin "23") (pinfunction "23_23") (pintype "bidirectional"))
    )
    (net (code "125") (name "/OUT_P22") (class "Default")
      (node (ref "J1") (pin "24") (pinfunction "24_24") (pintype "bidirectional"))
    )
    (net (code "126") (name "/OUT_P23") (class "Default")
      (node (ref "J1") (pin "25") (pinfunction "25_25") (pintype "bidirectional"))
    )
    (net (code "127") (name "/OUT_P24") (class "Default")
      (node (ref "J1") (pin "26") (pinfunction "26_26") (pintype "bidirectional"))
    )
    (net (code "128") (name "/OUT_P25") (class "Default")
      (node (ref "J1") (pin "27") (pinfunction "27_27") (pintype "bidirectional"))
    )
    (net (code "129") (name "/OUT_P26") (class "Default")
      (node (ref "J1") (pin "28") (pinfunction "28_28") (pintype "bidirectional"))
    )
    (net (code "130") (name "/OUT_P27") (class "Default")
      (node (ref "J1") (pin "29") (pinfunction "29_29") (pintype "bidirectional"))
    )
    (net (code "131") (name "/OUT_P28") (class "Default")
      (node (ref "J1") (pin "30") (pinfunction "30_30") (pintype "bidirectional"))
    )
    (net (code "132") (name "/OUT_P29") (class "Default")
      (node (ref "J1") (pin "31") (pinfunction "31_31") (pintype "bidirectional"))
    )
    (net (code "133") (name "/OUT_P30") (class "Default")
      (node (ref "J1") (pin "32") (pinfunction "32_32") (pintype "bidirectional"))
    )
    (net (code "134") (name "/OUT_P31") (class "Default")
      (node (ref "J1") (pin "33") (pinfunction "33_33") (pintype "bidirectional"))
    )
    (net (code "135") (name "/OUT_P32") (class "Default")
      (node (ref "J1") (pin "34") (pinfunction "34_34") (pintype "bidirectional"))
    )
    (net (code "138") (name "GND") (class "Default")
      (node (ref "C11") (pin "2") (pinfunction "2_2") (pintype "passive"))
      (node (ref "C15") (pin "2") (pinfunction "2_2") (pintype "passive"))
      (node (ref "J1") (pin "17") (pinfunction "17_17") (pintype "bidirectional"))
      (node (ref "J1") (pin "51") (pinfunction "51_51") (pintype "bidirectional"))
      (node (ref "J1") (pin "69") (pinfunction "69_69") (pintype "bidirectional"))
      (node (ref "J1") (pin "70") (pinfunction "70_70") (pintype "bidirectional"))
      (node (ref "J2") (pin "12") (pinfunction "12_12") (pintype "passive"))
      (node (ref "J2") (pin "15") (pinfunction "15_15") (pintype "passive"))
      (node (ref "J2") (pin "18") (pinfunction "18_18") (pintype "passive"))
      (node (ref "J2") (pin "21") (pinfunction "21_21") (pintype "passive"))
      (node (ref "J2") (pin "24") (pinfunction "24_24") (pintype "passive"))
      (node (ref "J2") (pin "3") (pinfunction "3_3") (pintype "passive"))
      (node (ref "J2") (pin "6") (pinfunction "6_6") (pintype "passive"))
      (node (ref "J2") (pin "9") (pinfunction "9_9") (pintype "passive"))
      (node (ref "J3") (pin "12") (pinfunction "12_12") (pintype "bidirectional"))
      (node (ref "J3") (pin "15") (pinfunction "15_15") (pintype "bidirectional"))
      (node (ref "J3") (pin "18") (pinfunction "18_18") (pintype "bidirectional"))
      (node (ref "J3") (pin "21") (pinfunction "21_21") (pintype "bidirectional"))
      (node (ref "J3") (pin "24") (pinfunction "24_24") (pintype "bidirectional"))
      (node (ref "J3") (pin "3") (pinfunction "3_3") (pintype "bidirectional"))
      (node (ref "J3") (pin "6") (pinfunction "6_6") (pintype "bidirectional"))
      (node (ref "J3") (pin "9") (pinfunction "9_9") (pintype "bidirectional"))
      (node (ref "J4") (pin "12") (pinfunction "12_12") (pintype "bidirectional"))
      (node (ref "J4") (pin "15") (pinfunction "15_15") (pintype "bidirectional"))
      (node (ref "J4") (pin "18") (pinfunction "18_18") (pintype "bidirectional"))
      (node (ref "J4") (pin "21") (pinfunction "21_21") (pintype "bidirectional"))
      (node (ref "J4") (pin "24") (pinfunction "24_24") (pintype "bidirectional"))
      (node (ref "J4") (pin "3") (pinfunction "3_3") (pintype "bidirectional"))
      (node (ref "J4") (pin "6") (pinfunction "6_6") (pintype "bidirectional"))
      (node (ref "J4") (pin "9") (pinfunction "9_9") (pintype "bidirectional"))
      (node (ref "J5") (pin "12") (pinfunction "12_12") (pintype "bidirectional"))
      (node (ref "J5") (pin "15") (pinfunction "15_15") (pintype "bidirectional"))
      (node (ref "J5") (pin "18") (pinfunction "18_18") (pintype "bidirectional"))
      (node (ref "J5") (pin "21") (pinfunction "21_21") (pintype "bidirectional"))
      (node (ref "J5") (pin "24") (pinfunction "24_24") (pintype "bidirectional"))
      (node (ref "J5") (pin "3") (pinfunction "3_3") (pintype "bidirectional"))
      (node (ref "J5") (pin "6") (pinfunction "6_6") (pintype "bidirectional"))
      (node (ref "J5") (pin "9") (pinfunction "9_9") (pintype "bidirectional"))
      (node (ref "J6") (pin "12") (pinfunction "12_12") (pintype "passive"))
      (node (ref "J6") (pin "15") (pinfunction "15_15") (pintype "passive"))
      (node (ref "J6") (pin "18") (pinfunction "18_18") (pintype "passive"))
      (node (ref "J6") (pin "21") (pinfunction "21_21") (pintype "passive"))
      (node (ref "J6") (pin "24") (pinfunction "24_24") (pintype "passive"))
      (node (ref "J6") (pin "3") (pinfunction "3_3") (pintype "passive"))
      (node (ref "J6") (pin "6") (pinfunction "6_6") (pintype "passive"))
      (node (ref "J6") (pin "9") (pinfunction "9_9") (pintype "passive"))
      (node (ref "J7") (pin "12") (pinfunction "12_12") (pintype "bidirectional"))
      (node (ref "J7") (pin "15") (pinfunction "15_15") (pintype "bidirectional"))
      (node (ref "J7") (pin "18") (pinfunction "18_18") (pintype "bidirectional"))
      (node (ref "J7") (pin "21") (pinfunction "21_21") (pintype "bidirectional"))
      (node (ref "J7") (pin "24") (pinfunction "24_24") (pintype "bidirectional"))
      (node (ref "J7") (pin "3") (pinfunction "3_3") (pintype "bidirectional"))
      (node (ref "J7") (pin "6") (pinfunction "6_6") (pintype "bidirectional"))
      (node (ref "J7") (pin "9") (pinfunction "9_9") (pintype "bidirectional"))
      (node (ref "J8") (pin "12") (pinfunction "12_12") (pintype "passive"))
      (node (ref "J8") (pin "15") (pinfunction "15_15") (pintype "passive"))
      (node (ref "J8") (pin "18") (pinfunction "18_18") (pintype "passive"))
      (node (ref "J8") (pin "21") (pinfunction "21_21") (pintype "passive"))
      (node (ref "J8") (pin "24") (pinfunction "24_24") (pintype "passive"))
      (node (ref "J8") (pin "3") (pinfunction "3_3") (pintype "passive"))
      (node (ref "J8") (pin "6") (pinfunction "6_6") (pintype "passive"))
      (node (ref "J8") (pin "9") (pinfunction "9_9") (pintype "passive"))
      (node (ref "J9") (pin "12") (pinfunction "12_12") (pintype "passive"))
      (node (ref "J9") (pin "15") (pinfunction "15_15") (pintype "passive"))
      (node (ref "J9") (pin "18") (pinfunction "18_18") (pintype "passive"))
      (node (ref "J9") (pin "21") (pinfunction "21_21") (pintype "passive"))
      (node (ref "J9") (pin "24") (pinfunction "24_24") (pintype "passive"))
      (node (ref "J9") (pin "3") (pinfunction "3_3") (pintype "passive"))
      (node (ref "J9") (pin "6") (pinfunction "6_6") (pintype "passive"))
      (node (ref "J9") (pin "9") (pinfunction "9_9") (pintype "passive"))
      (node (ref "R17") (pin "1") (pinfunction "1_1") (pintype "passive"))
      (node (ref "R23") (pin "1") (pinfunction "1_1") (pintype "passive"))
    )
    (net (code "139") (name "N13V0_SCSI") (class "Default")
      (node (ref "J1") (pin "52") (pinfunction "52_52") (pintype "bidirectional"))
      (node (ref "J2") (pin "26") (pinfunction "26_26") (pintype "passive"))
      (node (ref "J3") (pin "26") (pinfunction "26_26") (pintype "bidirectional"))
      (node (ref "J4") (pin "26") (pinfunction "26_26") (pintype "bidirectional"))
      (node (ref "J5") (pin "26") (pinfunction "26_26") (pintype "bidirectional"))
      (node (ref "J6") (pin "26") (pinfunction "26_26") (pintype "passive"))
      (node (ref "J7") (pin "26") (pinfunction "26_26") (pintype "bidirectional"))
      (node (ref "J8") (pin "26") (pinfunction "26_26") (pintype "passive"))
      (node (ref "J9") (pin "26") (pinfunction "26_26") (pintype "passive"))
    )
    (net (code "140") (name "Net-(B1-Pad1)") (class "Default")
      (node (ref "B1") (pin "1") (pinfunction "1_1") (pintype "bidirectional"))
      (node (ref "C11") (pin "1") (pinfunction "1_1") (pintype "passive"))
      (node (ref "R17") (pin "2") (pinfunction "2_2") (pintype "passive"))
    )
    (net (code "141") (name "Net-(B7-Pad1)") (class "Default")
      (node (ref "B7") (pin "1") (pinfunction "1_1") (pintype "bidirectional"))
      (node (ref "C15") (pin "1") (pinfunction "1_1") (pintype "passive"))
      (node (ref "R23") (pin "2") (pinfunction "2_2") (pintype "passive"))
    )
    (net (code "142") (name "P13V0_SCSI") (class "Default")
      (node (ref "J1") (pin "18") (pinfunction "18_18") (pintype "bidirectional"))
      (node (ref "J2") (pin "25") (pinfunction "25_25") (pintype "passive"))
      (node (ref "J3") (pin "25") (pinfunction "25_25") (pintype "bidirectional"))
      (node (ref "J4") (pin "25") (pinfunction "25_25") (pintype "bidirectional"))
      (node (ref "J5") (pin "25") (pinfunction "25_25") (pintype "bidirectional"))
      (node (ref "J6") (pin "25") (pinfunction "25_25") (pintype "passive"))
      (node (ref "J7") (pin "25") (pinfunction "25_25") (pintype "bidirectional"))
      (node (ref "J8") (pin "25") (pinfunction "25_25") (pintype "passive"))
      (node (ref "J9") (pin "25") (pinfunction "25_25") (pintype "passive"))
    )
  )
)
